# Sheet1-control.net
KiCad netlist of a schematic drawn in Altium Designer
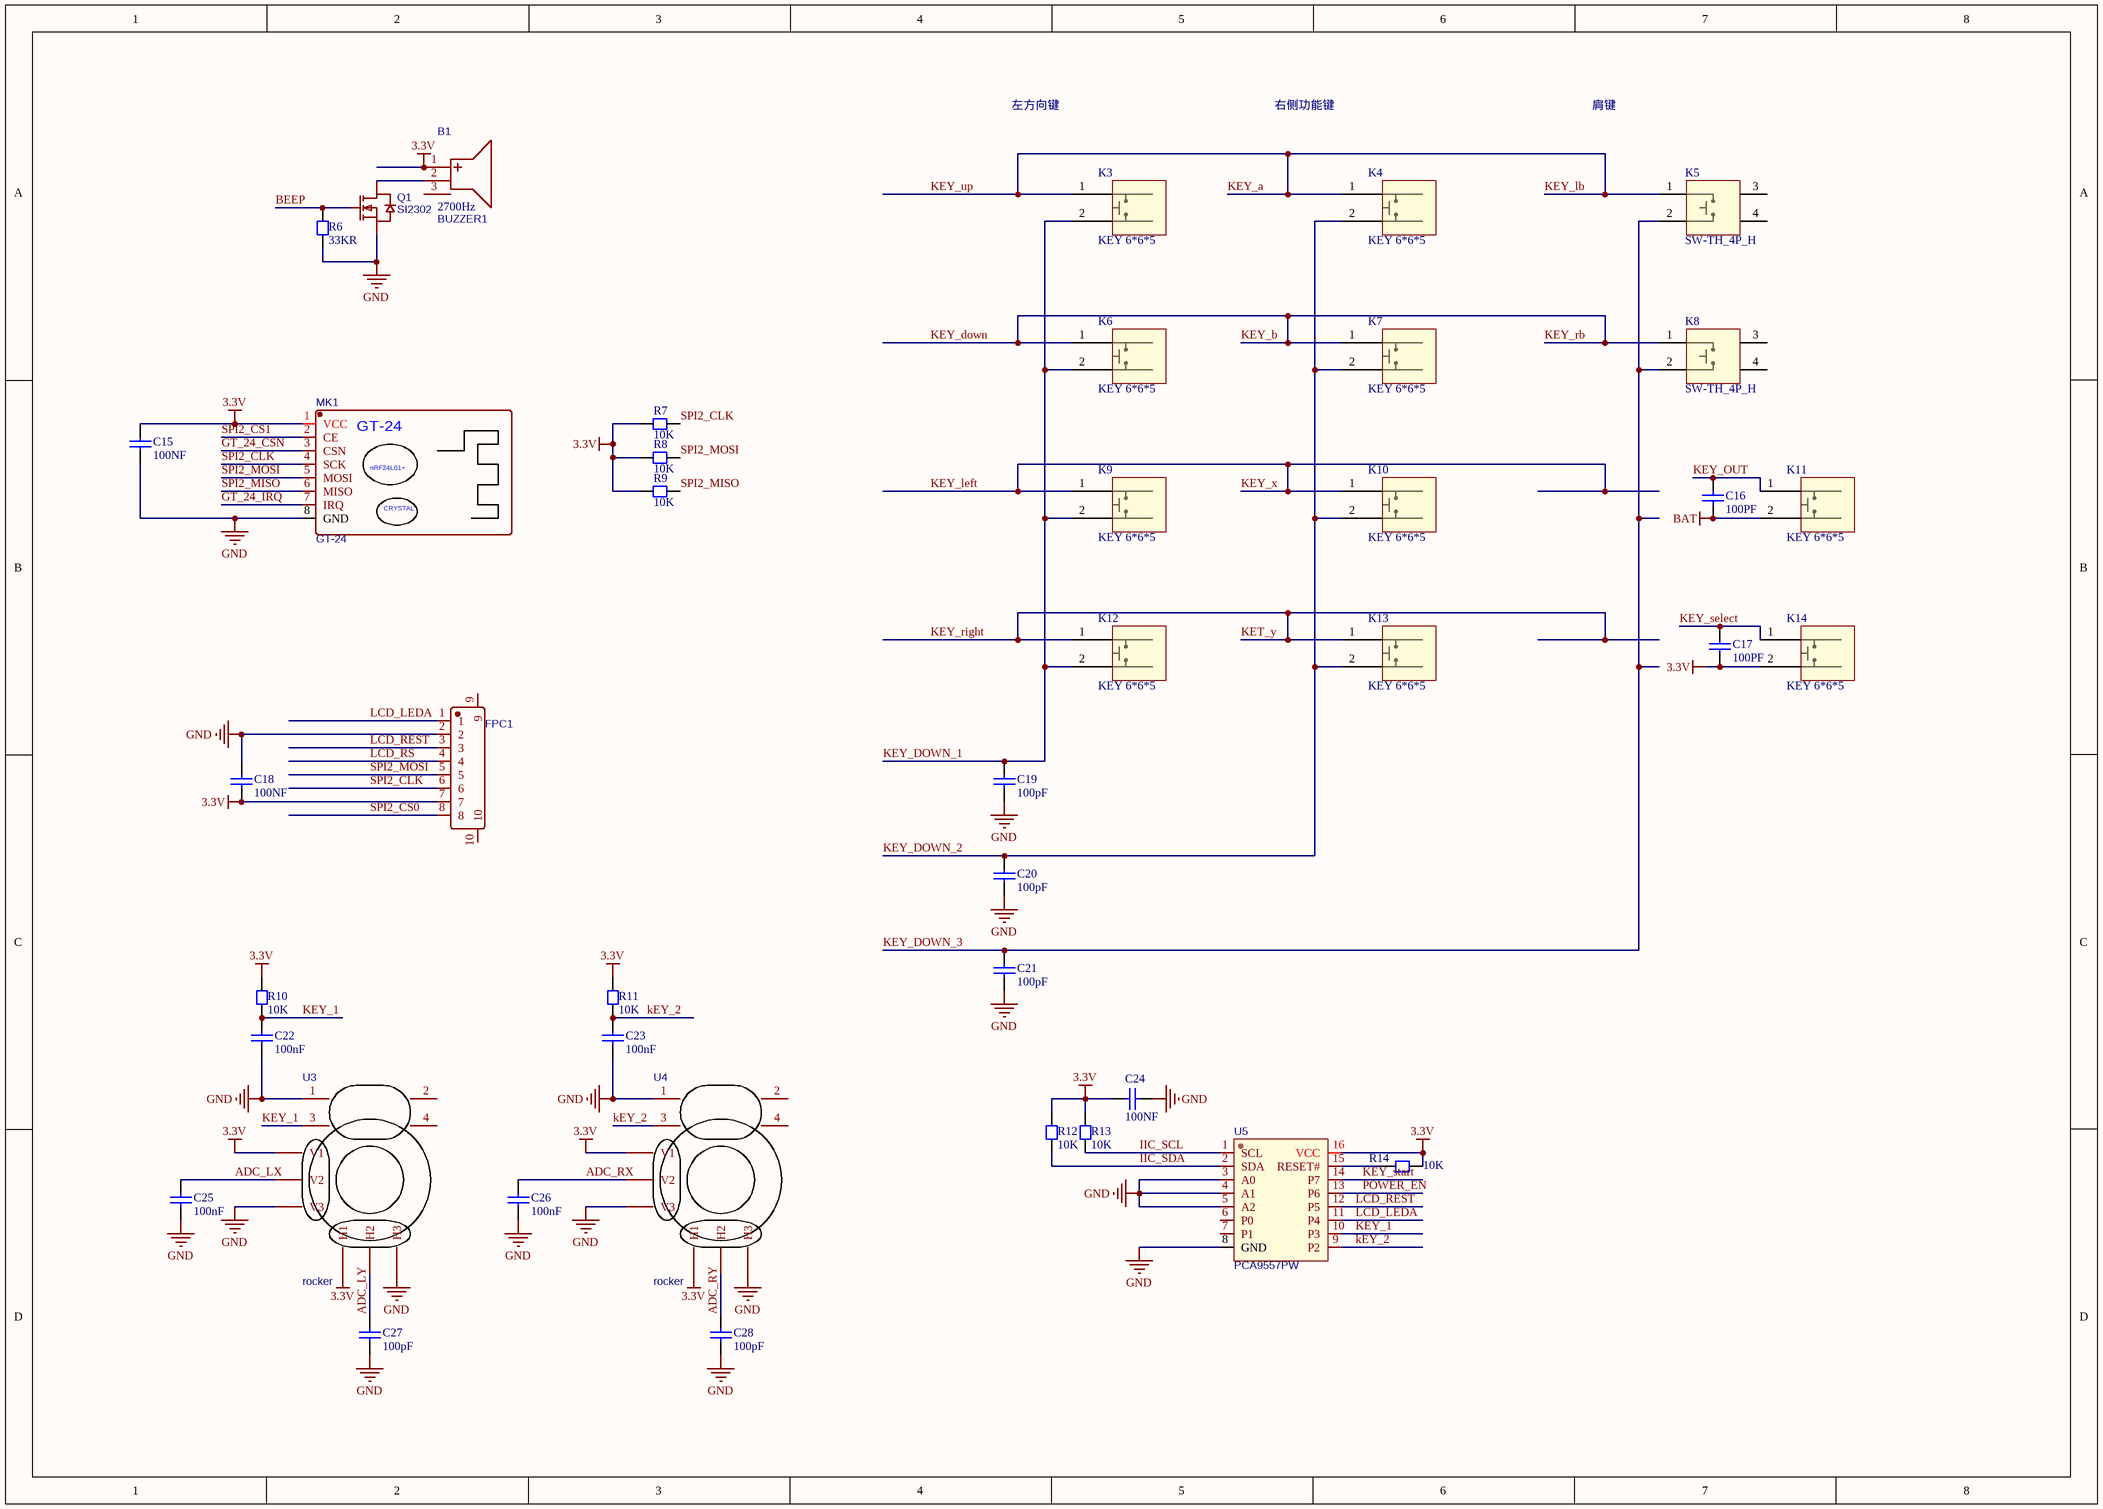
[diagram p0: Sheet1-control.SchDoc]

(export (version "E")
  (design (tool "Eeschema 10.0.6"))
  (components
    (comp (ref "B1")
      (value "BUZZER1")
      (footprint "BUZ-SMD_GSC7525RA")
      (description "2700Hz")
      (fields
        (field (name "MANUFACTURER") "INGHAi(赢海)")
        (field (name "MANUFACTURER PART") "GSC7525RA-16R2700")
        (field (name "CONTRIBUTOR") "LCSC")
      )
      (libsource (lib "base") (part "BUZZER1"))
    )
    (comp (ref "C15")
      (value "100NF")
      (footprint "CC1608-0603")
      (description "0603封装的电容")
      (fields (field (name "PUBLISHER") "Altium Limited"))
      (libsource (lib "base") (part "Cap Chip 0603"))
    )
    (comp (ref "C16")
      (value "100PF")
      (footprint "CC1608-0603")
      (description "0603封装的电容")
      (fields (field (name "PUBLISHER") "Altium Limited"))
      (libsource (lib "base") (part "Cap Chip 0603"))
    )
    (comp (ref "C17")
      (value "100PF")
      (footprint "CC1608-0603")
      (description "0603封装的电容")
      (fields (field (name "PUBLISHER") "Altium Limited"))
      (libsource (lib "base") (part "Cap Chip 0603"))
    )
    (comp (ref "C18")
      (value "100NF")
      (footprint "CC1608-0603")
      (description "0603封装的电容")
      (fields (field (name "PUBLISHER") "Altium Limited"))
      (libsource (lib "base") (part "Cap Chip 0603"))
    )
    (comp (ref "C19")
      (value "100pF")
      (footprint "CC1608-0603")
      (description "0603封装的电容")
      (fields (field (name "PUBLISHER") "Altium Limited"))
      (libsource (lib "base") (part "Cap Chip 0603"))
    )
    (comp (ref "C20")
      (value "100pF")
      (footprint "CC1608-0603")
      (description "0603封装的电容")
      (fields (field (name "PUBLISHER") "Altium Limited"))
      (libsource (lib "base") (part "Cap Chip 0603"))
    )
    (comp (ref "C21")
      (value "100pF")
      (footprint "CC1608-0603")
      (description "0603封装的电容")
      (fields (field (name "PUBLISHER") "Altium Limited"))
      (libsource (lib "base") (part "Cap Chip 0603"))
    )
    (comp (ref "C22")
      (value "100nF")
      (footprint "CC1608-0603")
      (description "0603封装的电容")
      (fields (field (name "PUBLISHER") "Altium Limited"))
      (libsource (lib "base") (part "Cap Chip 0603"))
    )
    (comp (ref "C23")
      (value "100nF")
      (footprint "CC1608-0603")
      (description "0603封装的电容")
      (fields (field (name "PUBLISHER") "Altium Limited"))
      (libsource (lib "base") (part "Cap Chip 0603"))
    )
    (comp (ref "C24")
      (value "100NF")
      (footprint "CC1608-0603")
      (description "0603封装的电容")
      (fields (field (name "PUBLISHER") "Altium Limited"))
      (libsource (lib "base") (part "Cap Chip 0603"))
    )
    (comp (ref "C25")
      (value "100nF")
      (footprint "CC1608-0603")
      (description "0603封装的电容")
      (fields (field (name "PUBLISHER") "Altium Limited"))
      (libsource (lib "base") (part "Cap Chip 0603"))
    )
    (comp (ref "C26")
      (value "100nF")
      (footprint "CC1608-0603")
      (description "0603封装的电容")
      (fields (field (name "PUBLISHER") "Altium Limited"))
      (libsource (lib "base") (part "Cap Chip 0603"))
    )
    (comp (ref "C27")
      (value "100pF")
      (footprint "CC1608-0603")
      (description "0603封装的电容")
      (fields (field (name "PUBLISHER") "Altium Limited"))
      (libsource (lib "base") (part "Cap Chip 0603"))
    )
    (comp (ref "C28")
      (value "100pF")
      (footprint "CC1608-0603")
      (description "0603封装的电容")
      (fields (field (name "PUBLISHER") "Altium Limited"))
      (libsource (lib "base") (part "Cap Chip 0603"))
    )
    (comp (ref "FPC1")
      (value "FFC 05 8P")
      (footprint "FFC-SMD_8P-P0.50")
      (fields
        (field (name "MANUFACTURER") "TXGA(特思嘉)")
        (field (name "MANUFACTURER PART") "FFC05001-08SBB124W5M-H")
        (field (name "CONTRIBUTOR") "LCSC")
      )
      (libsource (lib "Connectors") (part "FFC 05 8P"))
    )
    (comp (ref "K3")
      (value "KEY 6*6*5")
      (footprint "KEY 6*6*5")
      (description "无声轻触开关")
      (libsource (lib "base") (part "KEY 6*6*5"))
    )
    (comp (ref "K4")
      (value "KEY 6*6*5")
      (footprint "KEY 6*6*5")
      (description "无声轻触开关")
      (libsource (lib "base") (part "KEY 6*6*5"))
    )
    (comp (ref "K5")
      (value "SW-TH_4P_H")
      (footprint "SW-TH_KH-6X6X7H-ZJ")
      (description "卧式轻触开关")
      (libsource (lib "base") (part "SW-TH_4P_H"))
    )
    (comp (ref "K6")
      (value "KEY 6*6*5")
      (footprint "KEY 6*6*5")
      (description "无声轻触开关")
      (libsource (lib "base") (part "KEY 6*6*5"))
    )
    (comp (ref "K7")
      (value "KEY 6*6*5")
      (footprint "KEY 6*6*5")
      (description "无声轻触开关")
      (libsource (lib "base") (part "KEY 6*6*5"))
    )
    (comp (ref "K8")
      (value "SW-TH_4P_H")
      (footprint "SW-TH_KH-6X6X7H-ZJ")
      (description "卧式轻触开关")
      (libsource (lib "base") (part "SW-TH_4P_H"))
    )
    (comp (ref "K9")
      (value "KEY 6*6*5")
      (footprint "KEY 6*6*5")
      (description "无声轻触开关")
      (libsource (lib "base") (part "KEY 6*6*5"))
    )
    (comp (ref "K10")
      (value "KEY 6*6*5")
      (footprint "KEY 6*6*5")
      (description "无声轻触开关")
      (libsource (lib "base") (part "KEY 6*6*5"))
    )
    (comp (ref "K11")
      (value "KEY 6*6*5")
      (footprint "KEY 6*6*5")
      (description "无声轻触开关")
      (libsource (lib "base") (part "KEY 6*6*5"))
    )
    (comp (ref "K12")
      (value "KEY 6*6*5")
      (footprint "KEY 6*6*5")
      (description "无声轻触开关")
      (libsource (lib "base") (part "KEY 6*6*5"))
    )
    (comp (ref "K13")
      (value "KEY 6*6*5")
      (footprint "KEY 6*6*5")
      (description "无声轻触开关")
      (libsource (lib "base") (part "KEY 6*6*5"))
    )
    (comp (ref "K14")
      (value "KEY 6*6*5")
      (footprint "KEY 6*6*5")
      (description "无声轻触开关")
      (libsource (lib "base") (part "KEY 6*6*5"))
    )
    (comp (ref "MK1")
      (value "GT-24")
      (footprint "WIRELM-SMD_AS01-ML01S")
      (description "工业级GT-24数传无线模块 2.4G NRF24L01&PA+LNA")
      (fields (field (name "MANUFACTURER") "Ashining(泽耀科技)") (field (name "MANUFACTURER PART") "AS01-ML01S"))
      (libsource (lib "sensor") (part "GT-24"))
    )
    (comp (ref "Q1")
      (value "SI2302")
      (footprint "SOT-23")
      (fields
        (field (name "MANUFACTURER") "TWGMC(台湾迪嘉)")
        (field (name "MANUFACTURER PART") "SI2306")
        (field (name "CONTRIBUTOR") "LCSC")
      )
      (libsource (lib "transistor") (part "SI2302"))
    )
    (comp (ref "R6")
      (value "33KR")
      (footprint "CR1608-0603")
      (description "贴片电阻")
      (libsource (lib "tianxiaohua_Schlib") (part "Chip resistor"))
    )
    (comp (ref "R7")
      (value "10K")
      (footprint "CR1608-0603")
      (description "0603封装电阻")
      (fields (field (name "PUBLISHER") "Altium Limited"))
      (libsource (lib "base") (part "Resistor Chip 0603"))
    )
    (comp (ref "R8")
      (value "10K")
      (footprint "CR1608-0603")
      (description "0603封装电阻")
      (fields (field (name "PUBLISHER") "Altium Limited"))
      (libsource (lib "base") (part "Resistor Chip 0603"))
    )
    (comp (ref "R9")
      (value "10K")
      (footprint "CR1608-0603")
      (description "0603封装电阻")
      (fields (field (name "PUBLISHER") "Altium Limited"))
      (libsource (lib "base") (part "Resistor Chip 0603"))
    )
    (comp (ref "R10")
      (value "10K")
      (footprint "CR1608-0603")
      (description "0603封装电阻")
      (fields (field (name "PUBLISHER") "Altium Limited"))
      (libsource (lib "") (part "Resistor Chip 0603_1"))
    )
    (comp (ref "R11")
      (value "10K")
      (footprint "CR1608-0603")
      (description "0603封装电阻")
      (fields (field (name "PUBLISHER") "Altium Limited"))
      (libsource (lib "") (part "Resistor Chip 0603_1"))
    )
    (comp (ref "R12")
      (value "10K")
      (footprint "CR1608-0603")
      (description "0603封装电阻")
      (fields (field (name "PUBLISHER") "Altium Limited"))
      (libsource (lib "") (part "Resistor Chip 0603_2"))
    )
    (comp (ref "R13")
      (value "10K")
      (footprint "CR1608-0603")
      (description "0603封装电阻")
      (fields (field (name "PUBLISHER") "Altium Limited"))
      (libsource (lib "") (part "Resistor Chip 0603_2"))
    )
    (comp (ref "R14")
      (value "10K")
      (footprint "CR1608-0603")
      (description "0603封装电阻")
      (fields (field (name "PUBLISHER") "Altium Limited"))
      (libsource (lib "base") (part "Resistor Chip 0603"))
    )
    (comp (ref "U3")
      (value "rocker")
      (footprint "PCBComponent_1")
      (fields (field (name "MANUFACTURER PART") "摇杆") (field (name "CONTRIBUTOR") "Alex_Ai"))
      (libsource (lib "base") (part "rocker"))
    )
    (comp (ref "U4")
      (value "rocker")
      (footprint "PCBComponent_1")
      (fields (field (name "MANUFACTURER PART") "摇杆") (field (name "CONTRIBUTOR") "Alex_Ai"))
      (libsource (lib "base") (part "rocker"))
    )
    (comp (ref "U5")
      (value "PCA9557PW")
      (footprint "TSSOP-16")
      (description "TSSOP-16 8位I2C总线和SMBus I/O扩展器芯片")
      (fields (field (name "MANUFACTURER") "TI(德州仪器)") (field (name "CONTRIBUTOR") "LCSC"))
      (libsource (lib "PB-Chip") (part "PCA9557PW"))
    )
  )
  (nets
    (net (code "1") (name "/ADC_LX") (class "Default")
      (node (ref "C25") (pin "2") (pinfunction "2_2") (pintype "passive"))
      (node (ref "U3") (pin "6") (pinfunction "V2_6") (pintype "passive"))
    )
    (net (code "2") (name "/ADC_LY") (class "Default")
      (node (ref "C27") (pin "2") (pinfunction "2_2") (pintype "passive"))
      (node (ref "U3") (pin "9") (pinfunction "H2_9") (pintype "passive"))
    )
    (net (code "3") (name "/ADC_RX") (class "Default")
      (node (ref "C26") (pin "2") (pinfunction "2_2") (pintype "passive"))
      (node (ref "U4") (pin "6") (pinfunction "V2_6") (pintype "passive"))
    )
    (net (code "4") (name "/ADC_RY") (class "Default")
      (node (ref "C28") (pin "2") (pinfunction "2_2") (pintype "passive"))
      (node (ref "U4") (pin "9") (pinfunction "H2_9") (pintype "passive"))
    )
    (net (code "5") (name "/BEEP") (class "Default")
      (node (ref "Q1") (pin "1") (pinfunction "G_1") (pintype "passive"))
      (node (ref "R6") (pin "1") (pinfunction "1_1") (pintype "passive"))
    )
    (net (code "6") (name "/GT_24_CSN") (class "Default")
      (node (ref "MK1") (pin "3") (pinfunction "CSN_3") (pintype "passive"))
    )
    (net (code "7") (name "/GT_24_IRQ") (class "Default")
      (node (ref "MK1") (pin "7") (pinfunction "IRQ_7") (pintype "passive"))
    )
    (net (code "8") (name "/IIC_SCL") (class "Default")
      (node (ref "R13") (pin "2") (pinfunction "2_2") (pintype "passive"))
      (node (ref "U5") (pin "1") (pinfunction "SCL_1") (pintype "passive"))
    )
    (net (code "9") (name "/IIC_SDA") (class "Default")
      (node (ref "R12") (pin "2") (pinfunction "2_2") (pintype "passive"))
      (node (ref "U5") (pin "2") (pinfunction "SDA_2") (pintype "passive"))
    )
    (net (code "10") (name "/KET_y") (class "Default")
      (node (ref "K12") (pin "1") (pinfunction "1_1") (pintype "passive"))
      (node (ref "K13") (pin "1") (pinfunction "1_1") (pintype "passive"))
    )
    (net (code "11") (name "/KEY_1") (class "Default")
      (node (ref "C22") (pin "2") (pinfunction "2_2") (pintype "passive"))
      (node (ref "R10") (pin "1") (pinfunction "1_1") (pintype "passive"))
      (node (ref "U3") (pin "3") (pinfunction "3_3") (pintype "passive"))
      (node (ref "U5") (pin "10") (pinfunction "P3_10") (pintype "passive"))
    )
    (net (code "12") (name "/KEY_DOWN_1") (class "Default")
      (node (ref "C19") (pin "2") (pinfunction "2_2") (pintype "passive"))
      (node (ref "K12") (pin "2") (pinfunction "2_2") (pintype "passive"))
      (node (ref "K3") (pin "2") (pinfunction "2_2") (pintype "passive"))
      (node (ref "K6") (pin "2") (pinfunction "2_2") (pintype "passive"))
      (node (ref "K9") (pin "2") (pinfunction "2_2") (pintype "passive"))
    )
    (net (code "13") (name "/KEY_DOWN_2") (class "Default")
      (node (ref "C20") (pin "2") (pinfunction "2_2") (pintype "passive"))
      (node (ref "K10") (pin "2") (pinfunction "2_2") (pintype "passive"))
      (node (ref "K13") (pin "2") (pinfunction "2_2") (pintype "passive"))
      (node (ref "K4") (pin "2") (pinfunction "2_2") (pintype "passive"))
      (node (ref "K7") (pin "2") (pinfunction "2_2") (pintype "passive"))
    )
    (net (code "14") (name "/KEY_DOWN_3") (class "Default")
      (node (ref "C21") (pin "2") (pinfunction "2_2") (pintype "passive"))
      (node (ref "K5") (pin "2") (pinfunction "2_2") (pintype "passive"))
      (node (ref "K8") (pin "2") (pinfunction "2_2") (pintype "passive"))
    )
    (net (code "15") (name "/KEY_OUT") (class "Default")
      (node (ref "C16") (pin "1") (pinfunction "1_1") (pintype "passive"))
      (node (ref "K11") (pin "1") (pinfunction "1_1") (pintype "passive"))
    )
    (net (code "16") (name "/KEY_a") (class "Default")
      (node (ref "K3") (pin "1") (pinfunction "1_1") (pintype "passive"))
      (node (ref "K4") (pin "1") (pinfunction "1_1") (pintype "passive"))
      (node (ref "K5") (pin "1") (pinfunction "1_1") (pintype "passive"))
    )
    (net (code "17") (name "/KEY_b") (class "Default")
      (node (ref "K6") (pin "1") (pinfunction "1_1") (pintype "passive"))
      (node (ref "K7") (pin "1") (pinfunction "1_1") (pintype "passive"))
      (node (ref "K8") (pin "1") (pinfunction "1_1") (pintype "passive"))
    )
    (net (code "18") (name "/KEY_left") (class "Default")
      (node (ref "K10") (pin "1") (pinfunction "1_1") (pintype "passive"))
      (node (ref "K9") (pin "1") (pinfunction "1_1") (pintype "passive"))
    )
    (net (code "19") (name "/KEY_select") (class "Default")
      (node (ref "C17") (pin "1") (pinfunction "1_1") (pintype "passive"))
      (node (ref "K14") (pin "1") (pinfunction "1_1") (pintype "passive"))
    )
    (net (code "20") (name "/KEY_start") (class "Default")
      (node (ref "U5") (pin "14") (pinfunction "P7_14") (pintype "passive"))
    )
    (net (code "21") (name "/LCD_LEDA") (class "Default")
      (node (ref "FPC1") (pin "1") (pinfunction "1_1") (pintype "passive"))
      (node (ref "U5") (pin "11") (pinfunction "P4_11") (pintype "passive"))
    )
    (net (code "22") (name "/LCD_REST") (class "Default")
      (node (ref "FPC1") (pin "3") (pinfunction "3_3") (pintype "passive"))
      (node (ref "U5") (pin "12") (pinfunction "P5_12") (pintype "passive"))
    )
    (net (code "23") (name "/LCD_RS") (class "Default")
      (node (ref "FPC1") (pin "4") (pinfunction "4_4") (pintype "passive"))
    )
    (net (code "24") (name "/POWER_EN") (class "Default")
      (node (ref "U5") (pin "13") (pinfunction "P6_13") (pintype "passive"))
    )
    (net (code "25") (name "/SPI2_CLK") (class "Default")
      (node (ref "FPC1") (pin "6") (pinfunction "6_6") (pintype "passive"))
      (node (ref "MK1") (pin "4") (pinfunction "SCK_4") (pintype "passive"))
      (node (ref "R7") (pin "1") (pinfunction "1_1") (pintype "passive"))
    )
    (net (code "26") (name "/SPI2_CS0") (class "Default")
      (node (ref "FPC1") (pin "8") (pinfunction "8_8") (pintype "passive"))
    )
    (net (code "27") (name "/SPI2_CS1") (class "Default")
      (node (ref "MK1") (pin "2") (pinfunction "CE_2") (pintype "passive"))
    )
    (net (code "28") (name "/SPI2_MISO") (class "Default")
      (node (ref "MK1") (pin "6") (pinfunction "MISO_6") (pintype "passive"))
      (node (ref "R9") (pin "1") (pinfunction "1_1") (pintype "passive"))
    )
    (net (code "29") (name "/SPI2_MOSI") (class "Default")
      (node (ref "FPC1") (pin "5") (pinfunction "5_5") (pintype "passive"))
      (node (ref "MK1") (pin "5") (pinfunction "MOSI_5") (pintype "passive"))
      (node (ref "R8") (pin "1") (pinfunction "1_1") (pintype "passive"))
    )
    (net (code "30") (name "/kEY_2") (class "Default")
      (node (ref "C23") (pin "2") (pinfunction "2_2") (pintype "passive"))
      (node (ref "R11") (pin "1") (pinfunction "1_1") (pintype "passive"))
      (node (ref "U4") (pin "3") (pinfunction "3_3") (pintype "passive"))
      (node (ref "U5") (pin "9") (pinfunction "P2_9") (pintype "passive"))
    )
    (net (code "31") (name "3.3V") (class "Default")
      (node (ref "B1") (pin "1") (pinfunction "+_1") (pintype "passive"))
      (node (ref "C15") (pin "2") (pinfunction "2_2") (pintype "passive"))
      (node (ref "C17") (pin "2") (pinfunction "2_2") (pintype "passive"))
      (node (ref "C18") (pin "1") (pinfunction "1_1") (pintype "passive"))
      (node (ref "C24") (pin "2") (pinfunction "2_2") (pintype "passive"))
      (node (ref "FPC1") (pin "7") (pinfunction "7_7") (pintype "passive"))
      (node (ref "K14") (pin "2") (pinfunction "2_2") (pintype "passive"))
      (node (ref "MK1") (pin "1") (pinfunction "VCC_1") (pintype "passive"))
      (node (ref "R10") (pin "2") (pinfunction "2_2") (pintype "passive"))
      (node (ref "R11") (pin "2") (pinfunction "2_2") (pintype "passive"))
      (node (ref "R12") (pin "1") (pinfunction "1_1") (pintype "passive"))
      (node (ref "R13") (pin "1") (pinfunction "1_1") (pintype "passive"))
      (node (ref "R14") (pin "1") (pinfunction "1_1") (pintype "passive"))
      (node (ref "R7") (pin "2") (pinfunction "2_2") (pintype "passive"))
      (node (ref "R8") (pin "2") (pinfunction "2_2") (pintype "passive"))
      (node (ref "R9") (pin "2") (pinfunction "2_2") (pintype "passive"))
      (node (ref "U3") (pin "5") (pinfunction "V1_5") (pintype "passive"))
      (node (ref "U3") (pin "8") (pinfunction "H1_8") (pintype "passive"))
      (node (ref "U4") (pin "5") (pinfunction "V1_5") (pintype "passive"))
      (node (ref "U4") (pin "8") (pinfunction "H1_8") (pintype "passive"))
      (node (ref "U5") (pin "16") (pinfunction "VCC_16") (pintype "passive"))
    )
    (net (code "32") (name "BAT") (class "Default")
      (node (ref "C16") (pin "2") (pinfunction "2_2") (pintype "passive"))
      (node (ref "K11") (pin "2") (pinfunction "2_2") (pintype "passive"))
    )
    (net (code "33") (name "GND") (class "Default")
      (node (ref "C15") (pin "1") (pinfunction "1_1") (pintype "passive"))
      (node (ref "C18") (pin "2") (pinfunction "2_2") (pintype "passive"))
      (node (ref "C19") (pin "1") (pinfunction "1_1") (pintype "passive"))
      (node (ref "C20") (pin "1") (pinfunction "1_1") (pintype "passive"))
      (node (ref "C21") (pin "1") (pinfunction "1_1") (pintype "passive"))
      (node (ref "C22") (pin "1") (pinfunction "1_1") (pintype "passive"))
      (node (ref "C23") (pin "1") (pinfunction "1_1") (pintype "passive"))
      (node (ref "C24") (pin "1") (pinfunction "1_1") (pintype "passive"))
      (node (ref "C25") (pin "1") (pinfunction "1_1") (pintype "passive"))
      (node (ref "C26") (pin "1") (pinfunction "1_1") (pintype "passive"))
      (node (ref "C27") (pin "1") (pinfunction "1_1") (pintype "passive"))
      (node (ref "C28") (pin "1") (pinfunction "1_1") (pintype "passive"))
      (node (ref "FPC1") (pin "2") (pinfunction "2_2") (pintype "passive"))
      (node (ref "MK1") (pin "8") (pinfunction "GND_8") (pintype "passive"))
      (node (ref "Q1") (pin "2") (pinfunction "S_2") (pintype "passive"))
      (node (ref "R6") (pin "2") (pinfunction "2_2") (pintype "passive"))
      (node (ref "U3") (pin "1") (pinfunction "1_1") (pintype "passive"))
      (node (ref "U3") (pin "10") (pinfunction "H3_10") (pintype "passive"))
      (node (ref "U3") (pin "7") (pinfunction "V3_7") (pintype "passive"))
      (node (ref "U4") (pin "1") (pinfunction "1_1") (pintype "passive"))
      (node (ref "U4") (pin "10") (pinfunction "H3_10") (pintype "passive"))
      (node (ref "U4") (pin "7") (pinfunction "V3_7") (pintype "passive"))
      (node (ref "U5") (pin "3") (pinfunction "A0_3") (pintype "passive"))
      (node (ref "U5") (pin "4") (pinfunction "A1_4") (pintype "passive"))
      (node (ref "U5") (pin "5") (pinfunction "A2_5") (pintype "passive"))
      (node (ref "U5") (pin "8") (pinfunction "GND_8") (pintype "passive"))
    )
    (net (code "34") (name "Net-(B1--)") (class "Default")
      (node (ref "B1") (pin "2") (pinfunction "-_2") (pintype "passive"))
      (node (ref "Q1") (pin "3") (pinfunction "D_3") (pintype "passive"))
    )
    (net (code "35") (name "Net-(U5-RESET#)") (class "Default")
      (node (ref "R14") (pin "2") (pinfunction "2_2") (pintype "passive"))
      (node (ref "U5") (pin "15") (pinfunction "RESET#_15") (pintype "passive"))
    )
    (net (code "36") (name "unconnected-(B1-EH-Pad3)") (class "Default")
      (node (ref "B1") (pin "3") (pinfunction "EH_3") (pintype "passive"))
    )
    (net (code "37") (name "unconnected-(FPC1-Pad9)") (class "Default")
      (node (ref "FPC1") (pin "9") (pinfunction "9_9") (pintype "passive"))
    )
    (net (code "38") (name "unconnected-(FPC1-Pad10)") (class "Default")
      (node (ref "FPC1") (pin "10") (pinfunction "10_10") (pintype "passive"))
    )
    (net (code "39") (name "unconnected-(K5-Pad3)") (class "Default")
      (node (ref "K5") (pin "3") (pinfunction "3_3") (pintype "passive"))
    )
    (net (code "40") (name "unconnected-(K5-Pad4)") (class "Default")
      (node (ref "K5") (pin "4") (pinfunction "4_4") (pintype "passive"))
    )
    (net (code "41") (name "unconnected-(K8-Pad3)") (class "Default")
      (node (ref "K8") (pin "3") (pinfunction "3_3") (pintype "passive"))
    )
    (net (code "42") (name "unconnected-(K8-Pad4)") (class "Default")
      (node (ref "K8") (pin "4") (pinfunction "4_4") (pintype "passive"))
    )
    (net (code "43") (name "unconnected-(U3-Pad2)") (class "Default")
      (node (ref "U3") (pin "2") (pinfunction "2_2") (pintype "passive"))
    )
    (net (code "44") (name "unconnected-(U3-Pad4)") (class "Default")
      (node (ref "U3") (pin "4") (pinfunction "4_4") (pintype "passive"))
    )
    (net (code "45") (name "unconnected-(U4-Pad2)") (class "Default")
      (node (ref "U4") (pin "2") (pinfunction "2_2") (pintype "passive"))
    )
    (net (code "46") (name "unconnected-(U4-Pad4)") (class "Default")
      (node (ref "U4") (pin "4") (pinfunction "4_4") (pintype "passive"))
    )
    (net (code "47") (name "unconnected-(U5-P0-Pad6)") (class "Default")
      (node (ref "U5") (pin "6") (pinfunction "P0_6") (pintype "passive"))
    )
    (net (code "48") (name "unconnected-(U5-P1-Pad7)") (class "Default")
      (node (ref "U5") (pin "7") (pinfunction "P1_7") (pintype "passive"))
    )
  )
)
